# M115X.net
KiCad netlist of a schematic drawn in EAGLE
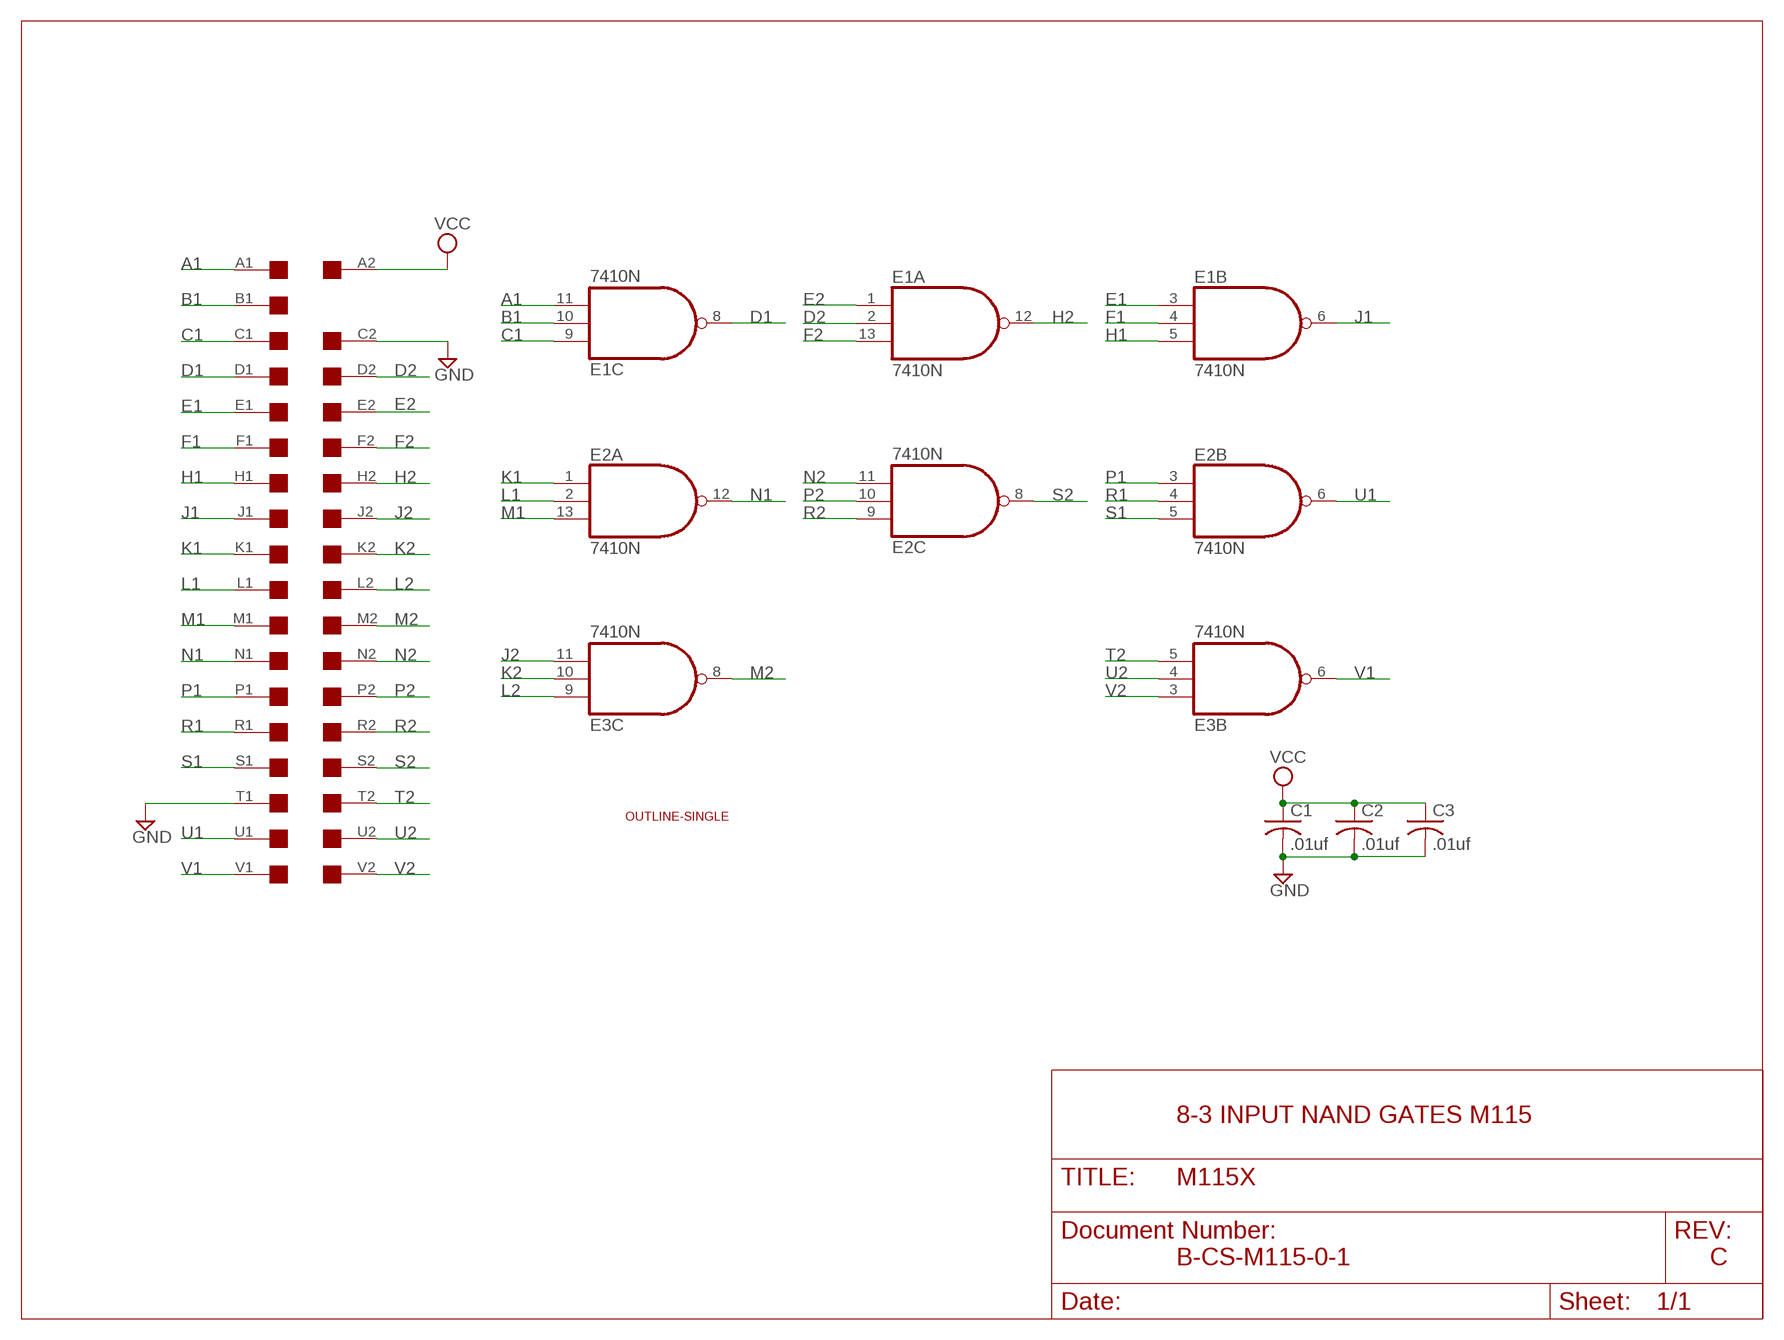
[diagram p0: schematic, sheet 1]

(export (version "E")
  (design (tool "Eeschema 10.0.6"))
  (components
    (comp (ref "C1")
      (value ".01uf")
      (footprint "eagle-import:C050-025X075")
      (libsource (lib "eagle-import") (part "C-US050-025X075"))
    )
    (comp (ref "C2")
      (value ".01uf")
      (footprint "eagle-import:C050-025X075")
      (libsource (lib "eagle-import") (part "C-US050-025X075"))
    )
    (comp (ref "C3")
      (value ".01uf")
      (footprint "eagle-import:C050-025X075")
      (libsource (lib "eagle-import") (part "C-US050-025X075"))
    )
    (comp (ref "E1")
      (value "7410N")
      (footprint "eagle-import:DIL14")
      (libsource (lib "eagle-import") (part "7410N"))
    )
    (comp (ref "E2")
      (value "7410N")
      (footprint "eagle-import:DIL14")
      (libsource (lib "eagle-import") (part "7410N"))
    )
    (comp (ref "E3")
      (value "7410N")
      (footprint "eagle-import:DIL14")
      (libsource (lib "eagle-import") (part "7410N"))
    )
    (comp (ref "U$1")
      (value "SINGLE")
      (footprint "eagle-import:EDGE-CON2")
      (libsource (lib "eagle-import") (part "SINGLE"))
    )
    (comp (ref "U$4")
      (value "OUTLINE-SINGLE")
      (footprint "eagle-import:SINGLE")
      (libsource (lib "eagle-import") (part "OUTLINE-SINGLE"))
    )
  )
  (nets
    (net (code "1") (name "/A1") (class "Default")
      (node (ref "E1") (pin "11") (pinfunction "I2_11") (pintype "input"))
      (node (ref "U$1") (pin "A1") (pinfunction "1_A1") (pintype "bidirectional"))
    )
    (net (code "2") (name "/B1") (class "Default")
      (node (ref "E1") (pin "10") (pinfunction "I1_10") (pintype "input"))
      (node (ref "U$1") (pin "B1") (pinfunction "1_B1") (pintype "bidirectional"))
    )
    (net (code "3") (name "/C1") (class "Default")
      (node (ref "E1") (pin "9") (pinfunction "I0_9") (pintype "input"))
      (node (ref "U$1") (pin "C1") (pinfunction "1_C1") (pintype "bidirectional"))
    )
    (net (code "4") (name "/D1") (class "Default")
      (node (ref "E1") (pin "8") (pinfunction "O_8") (pintype "output"))
      (node (ref "U$1") (pin "D1") (pinfunction "1_D1") (pintype "bidirectional"))
    )
    (net (code "5") (name "/D2") (class "Default")
      (node (ref "E1") (pin "2") (pinfunction "I1_2") (pintype "input"))
      (node (ref "U$1") (pin "D2") (pinfunction "1_D2") (pintype "bidirectional"))
    )
    (net (code "6") (name "/E1") (class "Default")
      (node (ref "E1") (pin "3") (pinfunction "I0_3") (pintype "input"))
      (node (ref "U$1") (pin "E1") (pinfunction "1_E1") (pintype "bidirectional"))
    )
    (net (code "7") (name "/E2") (class "Default")
      (node (ref "E1") (pin "1") (pinfunction "I0_1") (pintype "input"))
      (node (ref "U$1") (pin "E2") (pinfunction "1_E2") (pintype "bidirectional"))
    )
    (net (code "8") (name "/F1") (class "Default")
      (node (ref "E1") (pin "4") (pinfunction "I1_4") (pintype "input"))
      (node (ref "U$1") (pin "F1") (pinfunction "1_F1") (pintype "bidirectional"))
    )
    (net (code "9") (name "/F2") (class "Default")
      (node (ref "E1") (pin "13") (pinfunction "I2_13") (pintype "input"))
      (node (ref "U$1") (pin "F2") (pinfunction "1_F2") (pintype "bidirectional"))
    )
    (net (code "10") (name "/H1") (class "Default")
      (node (ref "E1") (pin "5") (pinfunction "I2_5") (pintype "input"))
      (node (ref "U$1") (pin "H1") (pinfunction "1_H1") (pintype "bidirectional"))
    )
    (net (code "11") (name "/H2") (class "Default")
      (node (ref "E1") (pin "12") (pinfunction "O_12") (pintype "output"))
      (node (ref "U$1") (pin "H2") (pinfunction "1_H2") (pintype "bidirectional"))
    )
    (net (code "12") (name "/J1") (class "Default")
      (node (ref "E1") (pin "6") (pinfunction "O_6") (pintype "output"))
      (node (ref "U$1") (pin "J1") (pinfunction "1_J1") (pintype "bidirectional"))
    )
    (net (code "13") (name "/J2") (class "Default")
      (node (ref "E3") (pin "11") (pinfunction "I2_11") (pintype "input"))
      (node (ref "U$1") (pin "J2") (pinfunction "1_J2") (pintype "bidirectional"))
    )
    (net (code "14") (name "/K1") (class "Default")
      (node (ref "E2") (pin "1") (pinfunction "I0_1") (pintype "input"))
      (node (ref "U$1") (pin "K1") (pinfunction "1_K1") (pintype "bidirectional"))
    )
    (net (code "15") (name "/K2") (class "Default")
      (node (ref "E3") (pin "10") (pinfunction "I1_10") (pintype "input"))
      (node (ref "U$1") (pin "K2") (pinfunction "1_K2") (pintype "bidirectional"))
    )
    (net (code "16") (name "/L1") (class "Default")
      (node (ref "E2") (pin "2") (pinfunction "I1_2") (pintype "input"))
      (node (ref "U$1") (pin "L1") (pinfunction "1_L1") (pintype "bidirectional"))
    )
    (net (code "17") (name "/L2") (class "Default")
      (node (ref "E3") (pin "9") (pinfunction "I0_9") (pintype "input"))
      (node (ref "U$1") (pin "L2") (pinfunction "1_L2") (pintype "bidirectional"))
    )
    (net (code "18") (name "/M1") (class "Default")
      (node (ref "E2") (pin "13") (pinfunction "I2_13") (pintype "input"))
      (node (ref "U$1") (pin "M1") (pinfunction "1_M1") (pintype "bidirectional"))
    )
    (net (code "19") (name "/M2") (class "Default")
      (node (ref "E3") (pin "8") (pinfunction "O_8") (pintype "output"))
      (node (ref "U$1") (pin "M2") (pinfunction "1_M2") (pintype "bidirectional"))
    )
    (net (code "20") (name "/N1") (class "Default")
      (node (ref "E2") (pin "12") (pinfunction "O_12") (pintype "output"))
      (node (ref "U$1") (pin "N1") (pinfunction "1_N1") (pintype "bidirectional"))
    )
    (net (code "21") (name "/N2") (class "Default")
      (node (ref "E2") (pin "11") (pinfunction "I2_11") (pintype "input"))
      (node (ref "U$1") (pin "N2") (pinfunction "1_N2") (pintype "bidirectional"))
    )
    (net (code "22") (name "/P1") (class "Default")
      (node (ref "E2") (pin "3") (pinfunction "I0_3") (pintype "input"))
      (node (ref "U$1") (pin "P1") (pinfunction "1_P1") (pintype "bidirectional"))
    )
    (net (code "23") (name "/P2") (class "Default")
      (node (ref "E2") (pin "10") (pinfunction "I1_10") (pintype "input"))
      (node (ref "U$1") (pin "P2") (pinfunction "1_P2") (pintype "bidirectional"))
    )
    (net (code "24") (name "/R1") (class "Default")
      (node (ref "E2") (pin "4") (pinfunction "I1_4") (pintype "input"))
      (node (ref "U$1") (pin "R1") (pinfunction "1_R1") (pintype "bidirectional"))
    )
    (net (code "25") (name "/R2") (class "Default")
      (node (ref "E2") (pin "9") (pinfunction "I0_9") (pintype "input"))
      (node (ref "U$1") (pin "R2") (pinfunction "1_R2") (pintype "bidirectional"))
    )
    (net (code "26") (name "/S1") (class "Default")
      (node (ref "E2") (pin "5") (pinfunction "I2_5") (pintype "input"))
      (node (ref "U$1") (pin "S1") (pinfunction "1_S1") (pintype "bidirectional"))
    )
    (net (code "27") (name "/S2") (class "Default")
      (node (ref "E2") (pin "8") (pinfunction "O_8") (pintype "output"))
      (node (ref "U$1") (pin "S2") (pinfunction "1_S2") (pintype "bidirectional"))
    )
    (net (code "28") (name "/T2") (class "Default")
      (node (ref "E3") (pin "5") (pinfunction "I2_5") (pintype "input"))
      (node (ref "U$1") (pin "T2") (pinfunction "1_T2") (pintype "bidirectional"))
    )
    (net (code "29") (name "/U1") (class "Default")
      (node (ref "E2") (pin "6") (pinfunction "O_6") (pintype "output"))
      (node (ref "U$1") (pin "U1") (pinfunction "1_U1") (pintype "bidirectional"))
    )
    (net (code "30") (name "/U2") (class "Default")
      (node (ref "E3") (pin "4") (pinfunction "I1_4") (pintype "input"))
      (node (ref "U$1") (pin "U2") (pinfunction "1_U2") (pintype "bidirectional"))
    )
    (net (code "31") (name "/V1") (class "Default")
      (node (ref "E3") (pin "6") (pinfunction "O_6") (pintype "output"))
      (node (ref "U$1") (pin "V1") (pinfunction "1_V1") (pintype "bidirectional"))
    )
    (net (code "32") (name "/V2") (class "Default")
      (node (ref "E3") (pin "3") (pinfunction "I0_3") (pintype "input"))
      (node (ref "U$1") (pin "V2") (pinfunction "1_V2") (pintype "bidirectional"))
    )
    (net (code "33") (name "GND") (class "Default")
      (node (ref "C1") (pin "2") (pinfunction "2_2") (pintype "passive"))
      (node (ref "C2") (pin "2") (pinfunction "2_2") (pintype "passive"))
      (node (ref "C3") (pin "2") (pinfunction "2_2") (pintype "passive"))
      (node (ref "U$1") (pin "C2") (pinfunction "1_C2") (pintype "bidirectional"))
      (node (ref "U$1") (pin "T1") (pinfunction "1_T1") (pintype "bidirectional"))
    )
    (net (code "34") (name "VCC") (class "Default")
      (node (ref "C1") (pin "1") (pinfunction "1_1") (pintype "passive"))
      (node (ref "C2") (pin "1") (pinfunction "1_1") (pintype "passive"))
      (node (ref "C3") (pin "1") (pinfunction "1_1") (pintype "passive"))
      (node (ref "U$1") (pin "A2") (pinfunction "1_A2") (pintype "bidirectional"))
    )
  )
)
